# design.net
KiCad netlist of a schematic drawn in Altium Designer
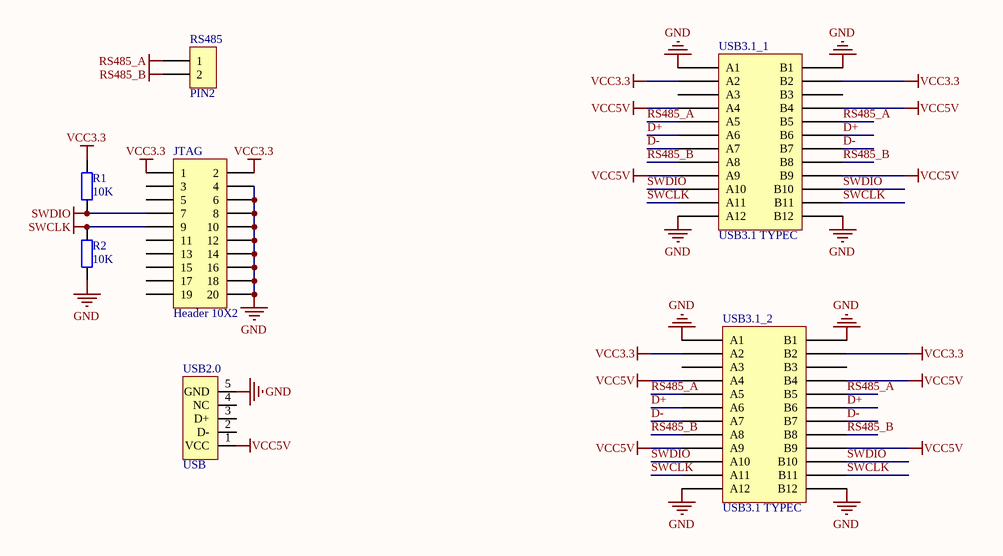
[diagram p0: 转接板.SchDoc]

(export (version "E")
  (design (tool "Eeschema 10.0.6"))
  (components
    (comp (ref "JTAG")
      (value "Header 10X2")
      (footprint "JTAG_20")
      (description "Header, 10-Pin, Dual row")
      (fields (field (name "PUBLISHER") "Altium Limited"))
      (libsource (lib "Miscellaneous Connectors") (part "Header 10X2"))
    )
    (comp (ref "R1")
      (value "10K")
      (footprint "0603")
      (description "Resistor")
      (fields (field (name "Comment") "Res2") (field (name "PUBLISHER") "Altium Limited"))
      (libsource (lib "Miscellaneous Devices") (part "Res2"))
    )
    (comp (ref "R2")
      (value "10K")
      (footprint "0603")
      (description "Resistor")
      (fields (field (name "Comment") "Res2") (field (name "PUBLISHER") "Altium Limited"))
      (libsource (lib "Miscellaneous Devices") (part "Res2"))
    )
    (comp (ref "RS485") (value "PIN2") (footprint "HEAD2L-0.8") (libsource (lib "MYLIB") (part "PIN2")))
    (comp (ref "USB2.0") (value "USB") (footprint "USB/SM0.8-6H5") (libsource (lib "MYLIB") (part "USB5")))
    (comp (ref "USB3.1_1")
      (value "USB3.1 TYPEC")
      (footprint "MicroUSB TypeC 3.1 - duplicate")
      (libsource (lib "MYLIB") (part "USB3.1 TYPEc"))
    )
    (comp (ref "USB3.1_2")
      (value "USB3.1 TYPEC")
      (footprint "MicroUSB TypeC 3.1 - duplicate")
      (libsource (lib "MYLIB") (part "USB3.1 TYPEc"))
    )
  )
  (nets
    (net (code "1") (name "/D+") (class "Default")
      (node (ref "USB3.1_1") (pin "19") (pinfunction "B6_19") (pintype "passive"))
      (node (ref "USB3.1_1") (pin "6") (pinfunction "A6_6") (pintype "passive"))
      (node (ref "USB3.1_2") (pin "19") (pinfunction "B6_19") (pintype "passive"))
      (node (ref "USB3.1_2") (pin "6") (pinfunction "A6_6") (pintype "passive"))
    )
    (net (code "2") (name "/D-") (class "Default")
      (node (ref "USB3.1_1") (pin "18") (pinfunction "B7_18") (pintype "passive"))
      (node (ref "USB3.1_1") (pin "7") (pinfunction "A7_7") (pintype "passive"))
      (node (ref "USB3.1_2") (pin "18") (pinfunction "B7_18") (pintype "passive"))
      (node (ref "USB3.1_2") (pin "7") (pinfunction "A7_7") (pintype "passive"))
    )
    (net (code "3") (name "GND") (class "Default")
      (node (ref "JTAG") (pin "10") (pinfunction "10_10") (pintype "passive"))
      (node (ref "JTAG") (pin "12") (pinfunction "12_12") (pintype "passive"))
      (node (ref "JTAG") (pin "14") (pinfunction "14_14") (pintype "passive"))
      (node (ref "JTAG") (pin "16") (pinfunction "16_16") (pintype "passive"))
      (node (ref "JTAG") (pin "18") (pinfunction "18_18") (pintype "passive"))
      (node (ref "JTAG") (pin "20") (pinfunction "20_20") (pintype "passive"))
      (node (ref "JTAG") (pin "4") (pinfunction "4_4") (pintype "passive"))
      (node (ref "JTAG") (pin "6") (pinfunction "6_6") (pintype "passive"))
      (node (ref "JTAG") (pin "8") (pinfunction "8_8") (pintype "passive"))
      (node (ref "R2") (pin "2") (pinfunction "2_2") (pintype "passive"))
      (node (ref "USB2.0") (pin "5") (pinfunction "GND_5") (pintype "passive"))
      (node (ref "USB3.1_1") (pin "1") (pinfunction "A1_1") (pintype "passive"))
      (node (ref "USB3.1_1") (pin "12") (pinfunction "A12_12") (pintype "passive"))
      (node (ref "USB3.1_1") (pin "13") (pinfunction "B12_13") (pintype "passive"))
      (node (ref "USB3.1_1") (pin "24") (pinfunction "B1_24") (pintype "passive"))
      (node (ref "USB3.1_2") (pin "1") (pinfunction "A1_1") (pintype "passive"))
      (node (ref "USB3.1_2") (pin "12") (pinfunction "A12_12") (pintype "passive"))
      (node (ref "USB3.1_2") (pin "13") (pinfunction "B12_13") (pintype "passive"))
      (node (ref "USB3.1_2") (pin "24") (pinfunction "B1_24") (pintype "passive"))
    )
    (net (code "4") (name "RS485_A") (class "Default")
      (node (ref "RS485") (pin "1") (pinfunction "1_1") (pintype "passive"))
      (node (ref "USB3.1_1") (pin "20") (pinfunction "B5_20") (pintype "passive"))
      (node (ref "USB3.1_1") (pin "5") (pinfunction "A5_5") (pintype "passive"))
      (node (ref "USB3.1_2") (pin "20") (pinfunction "B5_20") (pintype "passive"))
      (node (ref "USB3.1_2") (pin "5") (pinfunction "A5_5") (pintype "passive"))
    )
    (net (code "5") (name "RS485_B") (class "Default")
      (node (ref "RS485") (pin "2") (pinfunction "2_2") (pintype "passive"))
      (node (ref "USB3.1_1") (pin "17") (pinfunction "B8_17") (pintype "passive"))
      (node (ref "USB3.1_1") (pin "8") (pinfunction "A8_8") (pintype "passive"))
      (node (ref "USB3.1_2") (pin "17") (pinfunction "B8_17") (pintype "passive"))
      (node (ref "USB3.1_2") (pin "8") (pinfunction "A8_8") (pintype "passive"))
    )
    (net (code "6") (name "SWCLK") (class "Default")
      (node (ref "JTAG") (pin "9") (pinfunction "9_9") (pintype "passive"))
      (node (ref "R2") (pin "1") (pinfunction "1_1") (pintype "passive"))
      (node (ref "USB3.1_1") (pin "11") (pinfunction "A11_11") (pintype "passive"))
      (node (ref "USB3.1_1") (pin "14") (pinfunction "B11_14") (pintype "passive"))
      (node (ref "USB3.1_2") (pin "11") (pinfunction "A11_11") (pintype "passive"))
      (node (ref "USB3.1_2") (pin "14") (pinfunction "B11_14") (pintype "passive"))
    )
    (net (code "7") (name "SWDIO") (class "Default")
      (node (ref "JTAG") (pin "7") (pinfunction "7_7") (pintype "passive"))
      (node (ref "R1") (pin "2") (pinfunction "2_2") (pintype "passive"))
      (node (ref "USB3.1_1") (pin "10") (pinfunction "A10_10") (pintype "passive"))
      (node (ref "USB3.1_1") (pin "15") (pinfunction "B10_15") (pintype "passive"))
      (node (ref "USB3.1_2") (pin "10") (pinfunction "A10_10") (pintype "passive"))
      (node (ref "USB3.1_2") (pin "15") (pinfunction "B10_15") (pintype "passive"))
    )
    (net (code "8") (name "VCC3.3") (class "Default")
      (node (ref "JTAG") (pin "1") (pinfunction "1_1") (pintype "passive"))
      (node (ref "JTAG") (pin "2") (pinfunction "2_2") (pintype "passive"))
      (node (ref "R1") (pin "1") (pinfunction "1_1") (pintype "passive"))
      (node (ref "USB3.1_1") (pin "2") (pinfunction "A2_2") (pintype "passive"))
      (node (ref "USB3.1_1") (pin "23") (pinfunction "B2_23") (pintype "passive"))
      (node (ref "USB3.1_2") (pin "2") (pinfunction "A2_2") (pintype "passive"))
      (node (ref "USB3.1_2") (pin "23") (pinfunction "B2_23") (pintype "passive"))
    )
    (net (code "9") (name "VCC5V") (class "Default")
      (node (ref "USB2.0") (pin "1") (pinfunction "VCC_1") (pintype "passive"))
      (node (ref "USB3.1_1") (pin "16") (pinfunction "B9_16") (pintype "passive"))
      (node (ref "USB3.1_1") (pin "21") (pinfunction "B4_21") (pintype "passive"))
      (node (ref "USB3.1_1") (pin "4") (pinfunction "A4_4") (pintype "passive"))
      (node (ref "USB3.1_1") (pin "9") (pinfunction "A9_9") (pintype "passive"))
      (node (ref "USB3.1_2") (pin "16") (pinfunction "B9_16") (pintype "passive"))
      (node (ref "USB3.1_2") (pin "21") (pinfunction "B4_21") (pintype "passive"))
      (node (ref "USB3.1_2") (pin "4") (pinfunction "A4_4") (pintype "passive"))
      (node (ref "USB3.1_2") (pin "9") (pinfunction "A9_9") (pintype "passive"))
    )
    (net (code "10") (name "unconnected-(JTAG-Pad3)") (class "Default")
      (node (ref "JTAG") (pin "3") (pinfunction "3_3") (pintype "passive"))
    )
    (net (code "11") (name "unconnected-(JTAG-Pad5)") (class "Default")
      (node (ref "JTAG") (pin "5") (pinfunction "5_5") (pintype "passive"))
    )
    (net (code "12") (name "unconnected-(JTAG-Pad11)") (class "Default")
      (node (ref "JTAG") (pin "11") (pinfunction "11_11") (pintype "passive"))
    )
    (net (code "13") (name "unconnected-(JTAG-Pad13)") (class "Default")
      (node (ref "JTAG") (pin "13") (pinfunction "13_13") (pintype "passive"))
    )
    (net (code "14") (name "unconnected-(JTAG-Pad15)") (class "Default")
      (node (ref "JTAG") (pin "15") (pinfunction "15_15") (pintype "passive"))
    )
    (net (code "15") (name "unconnected-(JTAG-Pad17)") (class "Default")
      (node (ref "JTAG") (pin "17") (pinfunction "17_17") (pintype "passive"))
    )
    (net (code "16") (name "unconnected-(JTAG-Pad19)") (class "Default")
      (node (ref "JTAG") (pin "19") (pinfunction "19_19") (pintype "passive"))
    )
    (net (code "17") (name "unconnected-(USB2.0-D+-Pad3)") (class "Default")
      (node (ref "USB2.0") (pin "3") (pinfunction "D+_3") (pintype "passive"))
    )
    (net (code "18") (name "unconnected-(USB2.0-D--Pad2)") (class "Default")
      (node (ref "USB2.0") (pin "2") (pinfunction "D-_2") (pintype "passive"))
    )
    (net (code "19") (name "unconnected-(USB2.0-NC-Pad4)") (class "Default")
      (node (ref "USB2.0") (pin "4") (pinfunction "NC_4") (pintype "passive"))
    )
    (net (code "20") (name "unconnected-(USB3.1_1-A3-Pad3)") (class "Default")
      (node (ref "USB3.1_1") (pin "3") (pinfunction "A3_3") (pintype "passive"))
    )
    (net (code "21") (name "unconnected-(USB3.1_1-B3-Pad22)") (class "Default")
      (node (ref "USB3.1_1") (pin "22") (pinfunction "B3_22") (pintype "passive"))
    )
    (net (code "22") (name "unconnected-(USB3.1_2-A3-Pad3)") (class "Default")
      (node (ref "USB3.1_2") (pin "3") (pinfunction "A3_3") (pintype "passive"))
    )
    (net (code "23") (name "unconnected-(USB3.1_2-B3-Pad22)") (class "Default")
      (node (ref "USB3.1_2") (pin "22") (pinfunction "B3_22") (pintype "passive"))
    )
  )
)
